# EPS_DCDC_RLCL-FPF.net
KiCad netlist of a schematic drawn in Altium Designer
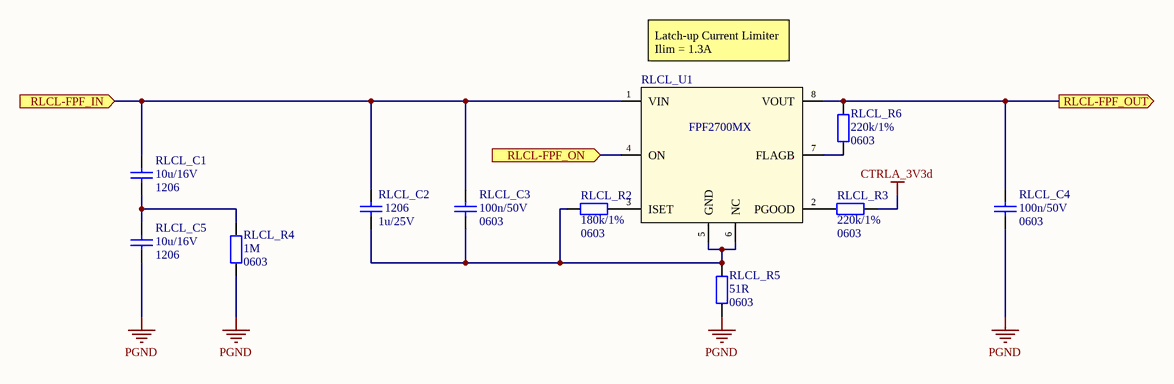
[diagram p0: EPS_DCDC_RLCL-FPF.SchDoc]

(export (version "E")
  (design (tool "Eeschema 10.0.6"))
  (components
    (comp (ref "RLCL_C1")
      (value "10u/16V")
      (footprint "SMD_Capacitor_1206")
      (description "Ceramic Cap Kemet COTS 10u/16V X7R 1206")
      (fields
        (field (name "MANUFACTURERPARTNUMBER") "C1206T106K4RACTU")
        (field (name "MANUFACTURER") "Kemet")
        (field (name "PACKGE") "1206")
      )
      (libsource (lib "capacitors") (part "Cer_C1206T106K4RACTU"))
    )
    (comp (ref "RLCL_C2")
      (value "1u/25V")
      (footprint "SMD_Capacitor_1206")
      (description "Ceramic Cap Kemet COTS 1u/25V X7R 1206")
      (fields
        (field (name "MANUFACTURERPARTNUMBER") "C1206T105K3RALTU")
        (field (name "MANUFACTURER") "Kemet")
        (field (name "PACKAGE") "1206")
      )
      (libsource (lib "capacitors") (part "Cer_C1206T105K3RALTU"))
    )
    (comp (ref "RLCL_C3")
      (value "100n/50V")
      (footprint "SMD_Capacitor_0603")
      (description "Ceramic Cap Murata Automotive 100n/50V X7R 0603")
      (fields
        (field (name "MANUFACTURER") "Murata")
        (field (name "MANUFACTURERPARTNUMBER") "GCJ188R71H104KA12D")
        (field (name "PACKAGE") "0603")
      )
      (libsource (lib "capacitors") (part "Cer_GCJ188R71H104KA12D"))
    )
    (comp (ref "RLCL_C4")
      (value "100n/50V")
      (footprint "SMD_Capacitor_0603")
      (description "Ceramic Cap Murata Automotive 100n/50V X7R 0603")
      (fields
        (field (name "MANUFACTURER") "Murata")
        (field (name "MANUFACTURERPARTNUMBER") "GCJ188R71H104KA12D")
        (field (name "PACKAGE") "0603")
      )
      (libsource (lib "capacitors") (part "Cer_GCJ188R71H104KA12D"))
    )
    (comp (ref "RLCL_C5")
      (value "10u/16V")
      (footprint "SMD_Capacitor_1206")
      (description "Ceramic Cap Kemet COTS 10u/16V X7R 1206")
      (fields
        (field (name "MANUFACTURERPARTNUMBER") "C1206T106K4RACTU")
        (field (name "MANUFACTURER") "Kemet")
        (field (name "PACKGE") "1206")
      )
      (libsource (lib "capacitors") (part "Cer_C1206T106K4RACTU"))
    )
    (comp (ref "RLCL_R2")
      (value "180k/1%")
      (footprint "SMD_Resistor_0603")
      (fields (field (name "PACKAGE") "0603"))
      (libsource (lib "") (part "Res_1"))
    )
    (comp (ref "RLCL_R3")
      (value "220k/1%")
      (footprint "SMD_Resistor_0603")
      (fields (field (name "PACKAGE") "0603"))
      (libsource (lib "") (part "Res_1"))
    )
    (comp (ref "RLCL_R4")
      (value "1M")
      (footprint "SMD_Resistor_0603")
      (fields (field (name "PACKAGE") "0603"))
      (libsource (lib "resistors") (part "Res"))
    )
    (comp (ref "RLCL_R5")
      (value "51R")
      (footprint "SMD_Resistor_0603")
      (fields (field (name "PACKAGE") "0603"))
      (libsource (lib "") (part "Res_2"))
    )
    (comp (ref "RLCL_R6")
      (value "220k/1%")
      (footprint "SMD_Resistor_0603")
      (fields (field (name "PACKAGE") "0603"))
      (libsource (lib "resistors") (part "Res"))
    )
    (comp (ref "RLCL_U1")
      (value "FPF2700MX")
      (footprint "SOIC-8-N")
      (description "Adj over-current protection 0.4-2A, Load Switch")
      (fields (field (name "MANUFACTURER") "Fairchild Semiconductor"))
      (libsource (lib "microcircuits") (part "FPF2700MX"))
    )
  )
  (nets
    (net (code "1") (name "/RLCL-FPF_IN") (class "Default")
      (node (ref "RLCL_C1") (pin "1") (pinfunction "1_1") (pintype "passive"))
      (node (ref "RLCL_C2") (pin "1") (pinfunction "1_1") (pintype "passive"))
      (node (ref "RLCL_C3") (pin "1") (pinfunction "1_1") (pintype "passive"))
      (node (ref "RLCL_U1") (pin "1") (pinfunction "VIN_1") (pintype "passive"))
    )
    (net (code "2") (name "/RLCL-FPF_ON") (class "Default")
      (node (ref "RLCL_U1") (pin "4") (pinfunction "ON_4") (pintype "passive"))
    )
    (net (code "3") (name "/RLCL-FPF_OUT") (class "Default")
      (node (ref "RLCL_C4") (pin "1") (pinfunction "1_1") (pintype "passive"))
      (node (ref "RLCL_R6") (pin "2") (pinfunction "2_2") (pintype "passive"))
      (node (ref "RLCL_U1") (pin "8") (pinfunction "VOUT_8") (pintype "passive"))
    )
    (net (code "4") (name "CTRLA_3V3d") (class "Default")
      (node (ref "RLCL_R3") (pin "2") (pinfunction "2_2") (pintype "passive"))
    )
    (net (code "5") (name "Net-(RLCL_C1-Pad2)") (class "Default")
      (node (ref "RLCL_C1") (pin "2") (pinfunction "2_2") (pintype "passive"))
      (node (ref "RLCL_C5") (pin "1") (pinfunction "1_1") (pintype "passive"))
      (node (ref "RLCL_R4") (pin "2") (pinfunction "2_2") (pintype "passive"))
    )
    (net (code "6") (name "Net-(RLCL_U1-FLAGB)") (class "Default")
      (node (ref "RLCL_R6") (pin "1") (pinfunction "1_1") (pintype "passive"))
      (node (ref "RLCL_U1") (pin "7") (pinfunction "FLAGB_7") (pintype "passive"))
    )
    (net (code "7") (name "Net-(RLCL_U1-GND)") (class "Default")
      (node (ref "RLCL_C2") (pin "2") (pinfunction "2_2") (pintype "passive"))
      (node (ref "RLCL_C3") (pin "2") (pinfunction "2_2") (pintype "passive"))
      (node (ref "RLCL_R2") (pin "1") (pinfunction "1_1") (pintype "passive"))
      (node (ref "RLCL_R5") (pin "1") (pinfunction "1_1") (pintype "passive"))
      (node (ref "RLCL_U1") (pin "5") (pinfunction "GND_5") (pintype "passive"))
      (node (ref "RLCL_U1") (pin "6") (pinfunction "NC_6") (pintype "passive"))
    )
    (net (code "8") (name "Net-(RLCL_U1-ISET)") (class "Default")
      (node (ref "RLCL_R2") (pin "2") (pinfunction "2_2") (pintype "passive"))
      (node (ref "RLCL_U1") (pin "3") (pinfunction "ISET_3") (pintype "passive"))
    )
    (net (code "9") (name "Net-(RLCL_U1-PGOOD)") (class "Default")
      (node (ref "RLCL_R3") (pin "1") (pinfunction "1_1") (pintype "passive"))
      (node (ref "RLCL_U1") (pin "2") (pinfunction "PGOOD_2") (pintype "passive"))
    )
    (net (code "10") (name "PGND") (class "Default")
      (node (ref "RLCL_C4") (pin "2") (pinfunction "2_2") (pintype "passive"))
      (node (ref "RLCL_C5") (pin "2") (pinfunction "2_2") (pintype "passive"))
      (node (ref "RLCL_R4") (pin "1") (pinfunction "1_1") (pintype "passive"))
      (node (ref "RLCL_R5") (pin "2") (pinfunction "2_2") (pintype "passive"))
    )
  )
)
